# SECDONGL_001.net
KiCad netlist of a schematic drawn in EAGLE
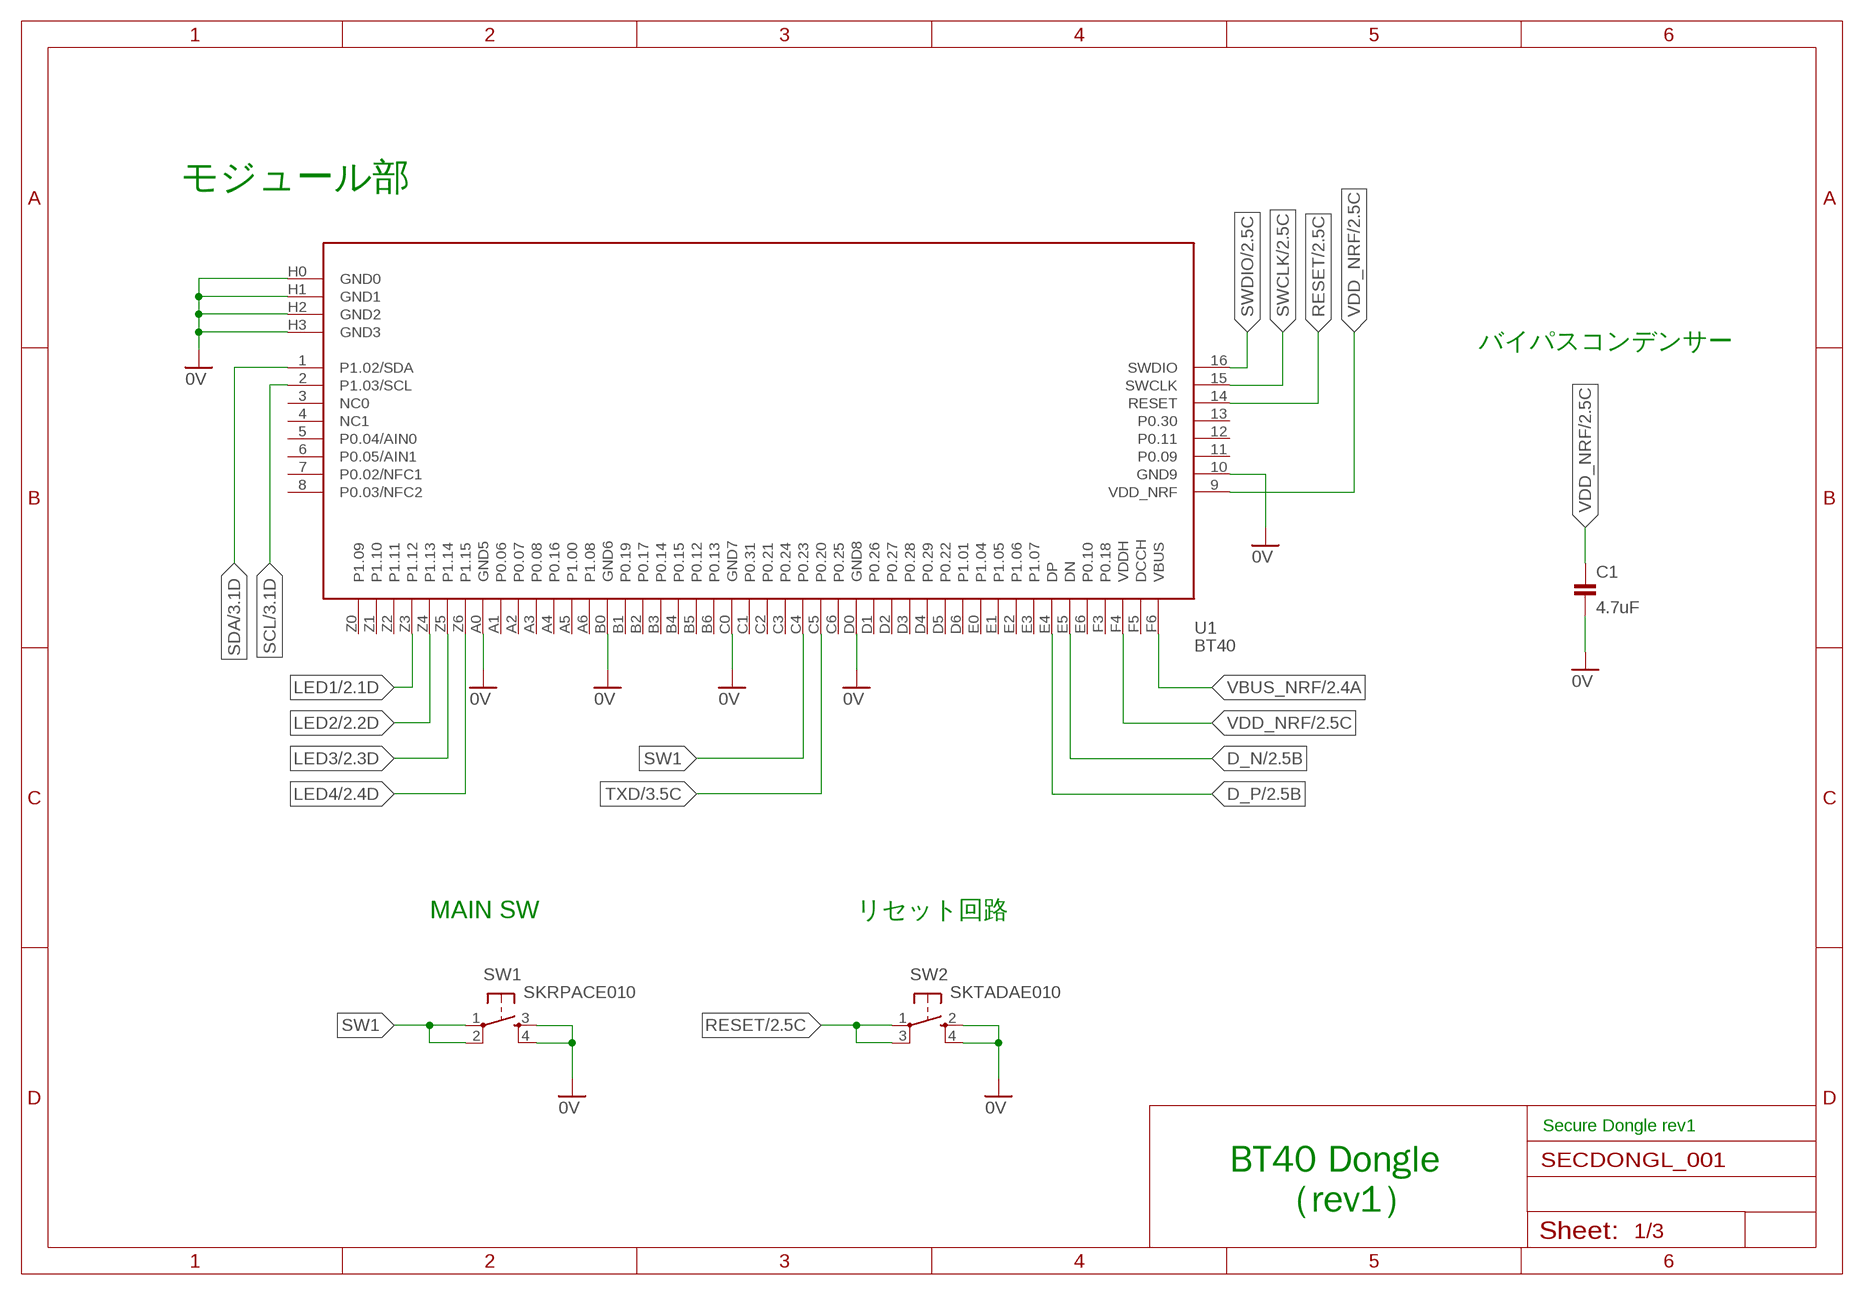
[diagram p0: schematic, sheet 1]
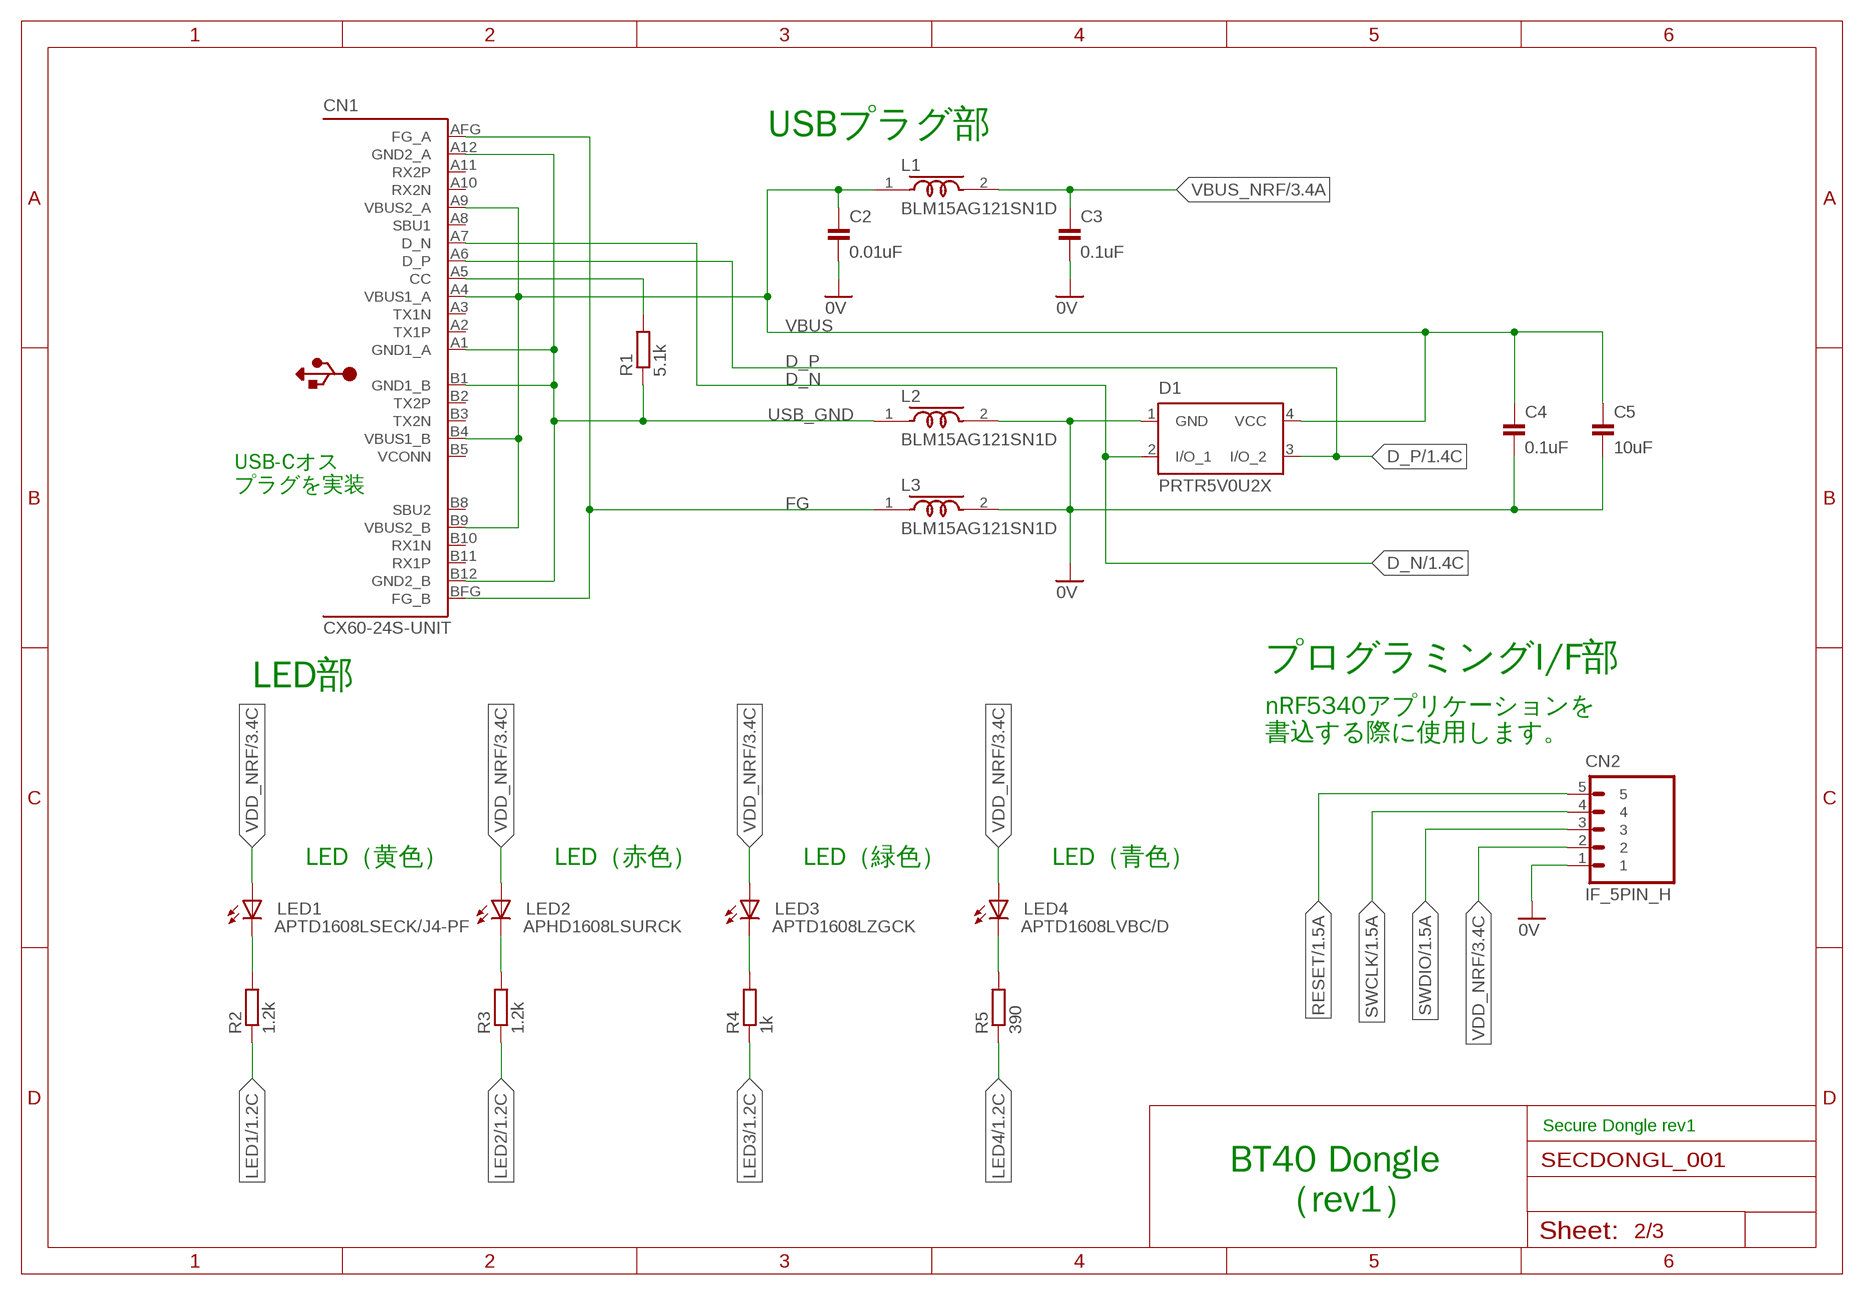
[diagram p1: schematic, sheet 2]
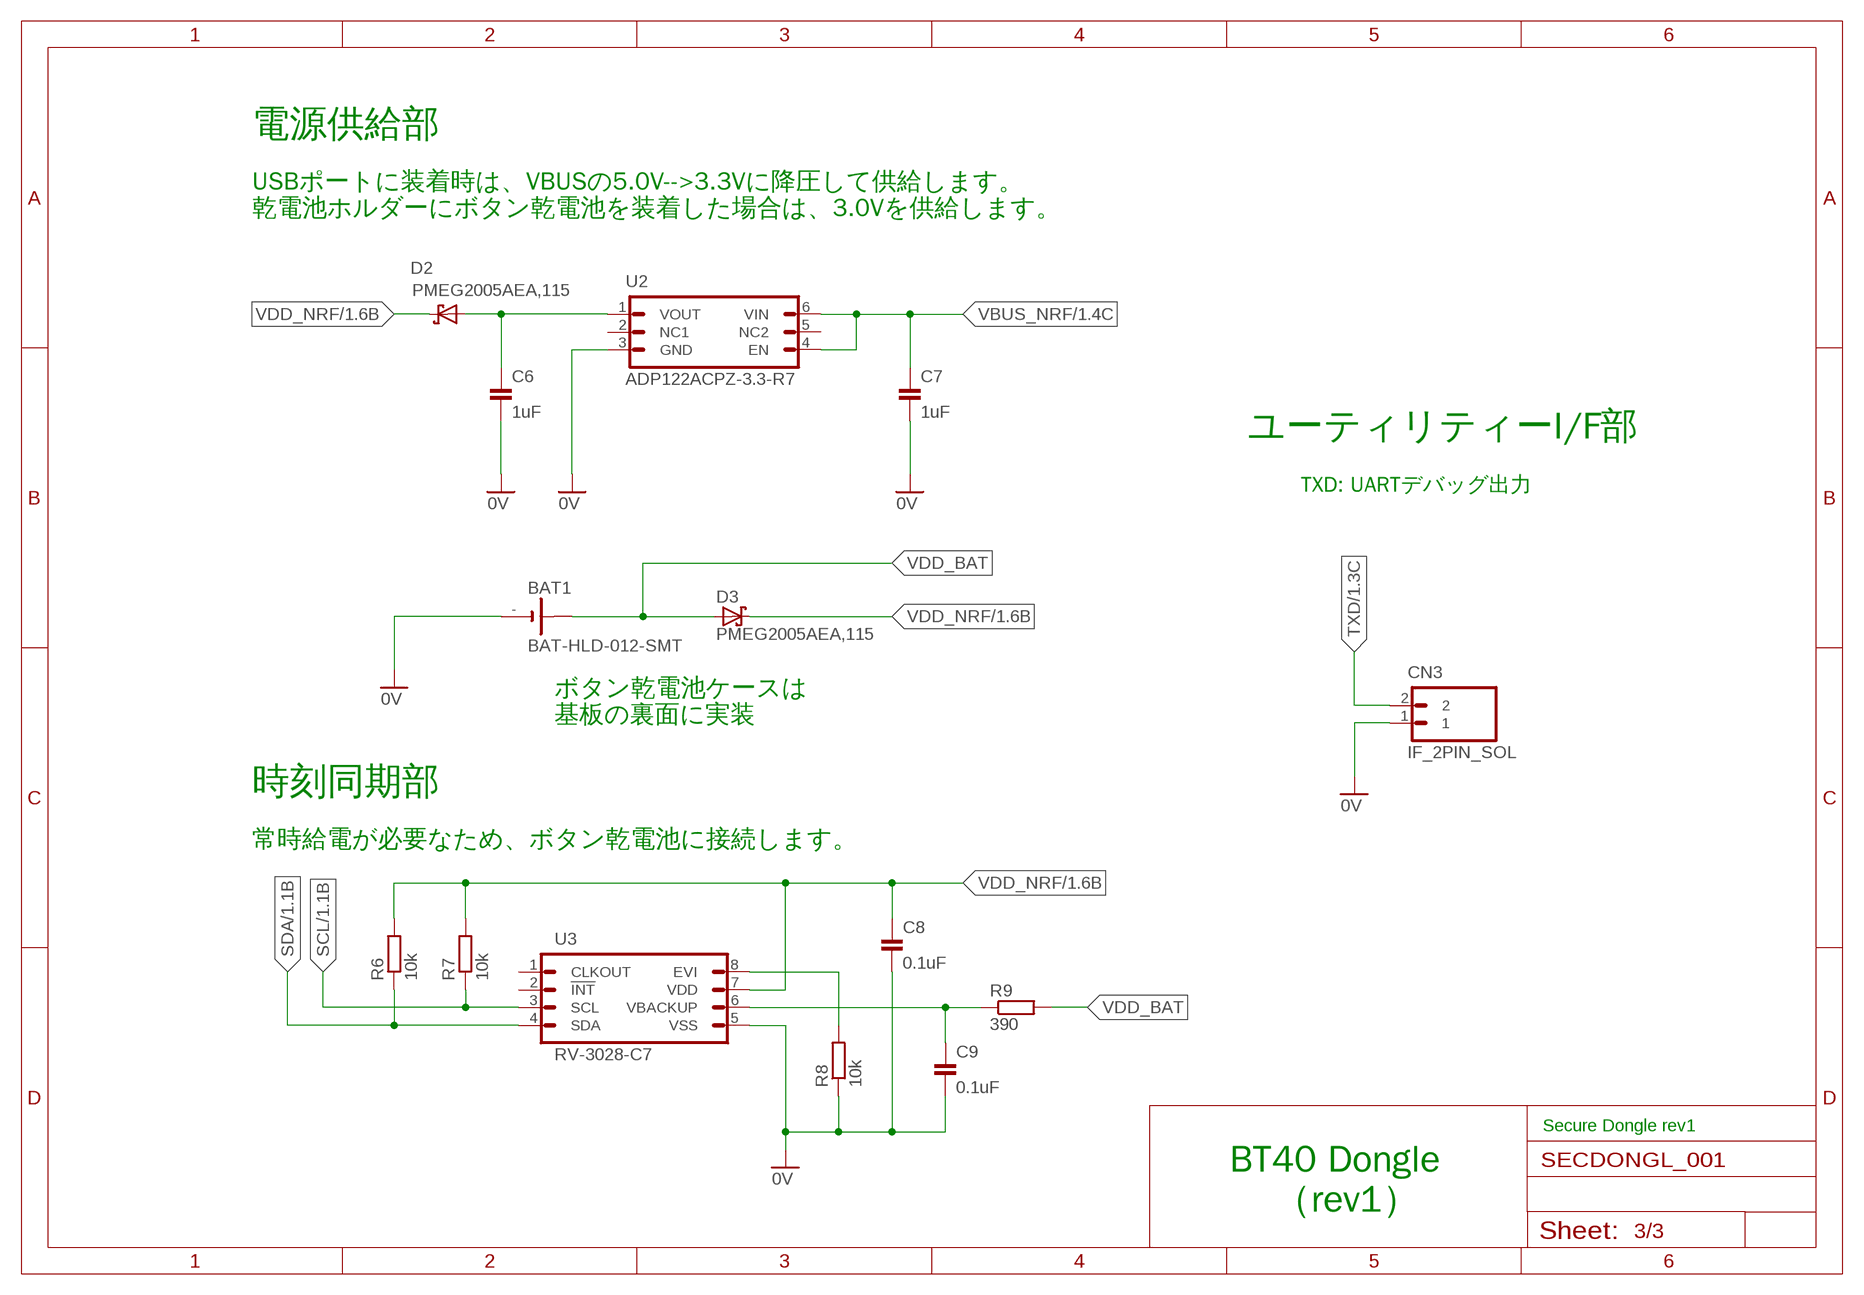
[diagram p2: schematic, sheet 3]

(export (version "E")
  (design (tool "Eeschema 10.0.6"))
  (components
    (comp (ref "BAT1")
      (value "BAT-HLD-012-SMT")
      (footprint "eagle-import:BAT-HLD-012-SMT")
      (libsource (lib "eagle-import") (part "BAT-HLD-012-SMT"))
    )
    (comp (ref "C6")
      (value "1uF")
      (footprint "eagle-import:C0603K")
      (libsource (lib "eagle-import") (part "CAP_0603"))
    )
    (comp (ref "C7")
      (value "1uF")
      (footprint "eagle-import:C0603K")
      (libsource (lib "eagle-import") (part "CAP_0603"))
    )
    (comp (ref "C8")
      (value "0.1uF")
      (footprint "eagle-import:C0402K")
      (libsource (lib "eagle-import") (part "CAP_0402K"))
    )
    (comp (ref "C9")
      (value "0.1uF")
      (footprint "eagle-import:C0402K")
      (libsource (lib "eagle-import") (part "CAP_0402K"))
    )
    (comp (ref "CN3")
      (value "IF_2PIN_SOL")
      (footprint "eagle-import:SOLPAD_2PIN")
      (libsource (lib "eagle-import") (part "IF_2PIN_SOL"))
    )
    (comp (ref "D2")
      (value "PMEG2005AEA,115")
      (footprint "eagle-import:SOD323-W")
      (libsource (lib "eagle-import") (part "PMEG2005AEA,115"))
    )
    (comp (ref "D3")
      (value "PMEG2005AEA,115")
      (footprint "eagle-import:SOD323-W")
      (libsource (lib "eagle-import") (part "PMEG2005AEA,115"))
    )
    (comp (ref "R6")
      (value "10k")
      (footprint "eagle-import:R0402")
      (libsource (lib "eagle-import") (part "RESISTOR_0402"))
    )
    (comp (ref "R7")
      (value "10k")
      (footprint "eagle-import:R0402")
      (libsource (lib "eagle-import") (part "RESISTOR_0402"))
    )
    (comp (ref "R8")
      (value "10k")
      (footprint "eagle-import:R0402")
      (libsource (lib "eagle-import") (part "RESISTOR_0402"))
    )
    (comp (ref "R9")
      (value "390")
      (footprint "eagle-import:R0402")
      (libsource (lib "eagle-import") (part "RESISTOR_0402"))
    )
    (comp (ref "U2")
      (value "ADP122ACPZ-3.3-R7")
      (footprint "eagle-import:6-LFCSP_UD")
      (libsource (lib "eagle-import") (part "ADP122ACPZ-3.3-R7"))
    )
    (comp (ref "U3")
      (value "RV-3028-C7")
      (footprint "eagle-import:SON-8")
      (libsource (lib "eagle-import") (part "RV-3028-C7"))
    )
    (comp (ref "C1")
      (value "4.7uF")
      (footprint "eagle-import:C0603K")
      (libsource (lib "eagle-import") (part "CAP_0603"))
    )
    (comp (ref "SW1")
      (value "SKRPACE010")
      (footprint "eagle-import:SKRPACE010")
      (libsource (lib "eagle-import") (part "SKRPACE010"))
    )
    (comp (ref "SW2")
      (value "SKTADAE010")
      (footprint "eagle-import:SKTADAE010")
      (libsource (lib "eagle-import") (part "SKTADAE010"))
    )
    (comp (ref "U1")
      (value "BT40")
      (footprint "eagle-import:BM40-B_1PRIMARY")
      (libsource (lib "eagle-import") (part "BT40"))
    )
    (comp (ref "C2")
      (value "0.01uF")
      (footprint "eagle-import:C0402K")
      (libsource (lib "eagle-import") (part "CAP_0402K"))
    )
    (comp (ref "C3")
      (value "0.1uF")
      (footprint "eagle-import:C0402K")
      (libsource (lib "eagle-import") (part "CAP_0402K"))
    )
    (comp (ref "C4")
      (value "0.1uF")
      (footprint "eagle-import:C0402K")
      (libsource (lib "eagle-import") (part "CAP_0402K"))
    )
    (comp (ref "C5")
      (value "10uF")
      (footprint "eagle-import:C0603K")
      (libsource (lib "eagle-import") (part "CAP_0603"))
    )
    (comp (ref "CN1")
      (value "CX60-24S-UNIT")
      (footprint "eagle-import:CX60-24S-UNIT")
      (libsource (lib "eagle-import") (part "CX60-24S-UNIT"))
    )
    (comp (ref "CN2")
      (value "IF_5PIN_H")
      (footprint "eagle-import:HEADER_5PIN")
      (libsource (lib "eagle-import") (part "IF_5PIN_H"))
    )
    (comp (ref "D1")
      (value "PRTR5V0U2X")
      (footprint "eagle-import:SOT143B")
      (libsource (lib "eagle-import") (part "PRTR5V0U2X"))
    )
    (comp (ref "L1")
      (value "BLM15AG121SN1D")
      (footprint "eagle-import:C0402K")
      (libsource (lib "eagle-import") (part "BLM15AG121SN1D"))
    )
    (comp (ref "L2")
      (value "BLM15AG121SN1D")
      (footprint "eagle-import:C0402K")
      (libsource (lib "eagle-import") (part "BLM15AG121SN1D"))
    )
    (comp (ref "L3")
      (value "BLM15AG121SN1D")
      (footprint "eagle-import:C0402K")
      (libsource (lib "eagle-import") (part "BLM15AG121SN1D"))
    )
    (comp (ref "LED1")
      (value "APTD1608LSECK/J4-PF")
      (footprint "eagle-import:APTD1608")
      (libsource (lib "eagle-import") (part "APTD1608LSECK/J4-PF"))
    )
    (comp (ref "LED2")
      (value "APHD1608LSURCK")
      (footprint "eagle-import:APTD1608")
      (libsource (lib "eagle-import") (part "APHD1608LSURCK"))
    )
    (comp (ref "LED3")
      (value "APTD1608LZGCK")
      (footprint "eagle-import:APTD1608")
      (libsource (lib "eagle-import") (part "APTD1608LZGCK"))
    )
    (comp (ref "LED4")
      (value "APTD1608LVBC/D")
      (footprint "eagle-import:APTD1608")
      (libsource (lib "eagle-import") (part "APTD1608LVBC/D"))
    )
    (comp (ref "R1")
      (value "5.1k")
      (footprint "eagle-import:R0402")
      (libsource (lib "eagle-import") (part "RESISTOR_0402"))
    )
    (comp (ref "R2")
      (value "1.2k")
      (footprint "eagle-import:R0402")
      (libsource (lib "eagle-import") (part "RESISTOR_0402"))
    )
    (comp (ref "R3")
      (value "1.2k")
      (footprint "eagle-import:R0402")
      (libsource (lib "eagle-import") (part "RESISTOR_0402"))
    )
    (comp (ref "R4")
      (value "1k")
      (footprint "eagle-import:R0402")
      (libsource (lib "eagle-import") (part "RESISTOR_0402"))
    )
    (comp (ref "R5")
      (value "390")
      (footprint "eagle-import:R0402")
      (libsource (lib "eagle-import") (part "RESISTOR_0402"))
    )
  )
  (nets
    (net (code "1") (name "0V") (class "Default")
      (node (ref "BAT1") (pin "-") (pinfunction "-_-") (pintype "passive"))
      (node (ref "C1") (pin "2") (pinfunction "2_2") (pintype "passive"))
      (node (ref "C2") (pin "2") (pinfunction "2_2") (pintype "passive"))
      (node (ref "C3") (pin "2") (pinfunction "2_2") (pintype "passive"))
      (node (ref "C4") (pin "2") (pinfunction "2_2") (pintype "passive"))
      (node (ref "C5") (pin "2") (pinfunction "2_2") (pintype "passive"))
      (node (ref "C6") (pin "2") (pinfunction "2_2") (pintype "passive"))
      (node (ref "C7") (pin "2") (pinfunction "2_2") (pintype "passive"))
      (node (ref "C8") (pin "2") (pinfunction "2_2") (pintype "passive"))
      (node (ref "C9") (pin "2") (pinfunction "2_2") (pintype "passive"))
      (node (ref "CN2") (pin "1") (pinfunction "1_1") (pintype "passive"))
      (node (ref "CN3") (pin "1") (pinfunction "1_1") (pintype "passive"))
      (node (ref "D1") (pin "1") (pinfunction "GND_1") (pintype "passive"))
      (node (ref "L2") (pin "2") (pinfunction "2_2") (pintype "passive"))
      (node (ref "L3") (pin "2") (pinfunction "2_2") (pintype "passive"))
      (node (ref "R8") (pin "1") (pinfunction "1_1") (pintype "passive"))
      (node (ref "SW1") (pin "3") (pinfunction "S_3") (pintype "passive"))
      (node (ref "SW1") (pin "4") (pinfunction "S1_4") (pintype "passive"))
      (node (ref "SW2") (pin "2") (pinfunction "S_2") (pintype "passive"))
      (node (ref "SW2") (pin "4") (pinfunction "S1_4") (pintype "passive"))
      (node (ref "U1") (pin "10") (pinfunction "GND9_10") (pintype "passive"))
      (node (ref "U1") (pin "A0") (pinfunction "GND5_A0") (pintype "passive"))
      (node (ref "U1") (pin "B0") (pinfunction "GND6_B0") (pintype "passive"))
      (node (ref "U1") (pin "C0") (pinfunction "GND7_C0") (pintype "passive"))
      (node (ref "U1") (pin "D0") (pinfunction "GND8_D0") (pintype "passive"))
      (node (ref "U1") (pin "H0") (pinfunction "GND0_H0") (pintype "passive"))
      (node (ref "U1") (pin "H1") (pinfunction "GND1_H1") (pintype "passive"))
      (node (ref "U1") (pin "H2") (pinfunction "GND2_H2") (pintype "passive"))
      (node (ref "U1") (pin "H3") (pinfunction "GND3_H3") (pintype "passive"))
      (node (ref "U2") (pin "3") (pinfunction "GND_3") (pintype "passive"))
      (node (ref "U3") (pin "5") (pinfunction "VSS_5") (pintype "passive"))
    )
    (net (code "2") (name "D_N") (class "Default")
      (node (ref "CN1") (pin "A7") (pinfunction "D_N_A7") (pintype "bidirectional"))
      (node (ref "D1") (pin "2") (pinfunction "I/O_1_2") (pintype "bidirectional"))
      (node (ref "U1") (pin "E5") (pinfunction "DN_E5") (pintype "bidirectional"))
    )
    (net (code "3") (name "D_P") (class "Default")
      (node (ref "CN1") (pin "A6") (pinfunction "D_P_A6") (pintype "bidirectional"))
      (node (ref "D1") (pin "3") (pinfunction "I/O_2_3") (pintype "bidirectional"))
      (node (ref "U1") (pin "E4") (pinfunction "DP_E4") (pintype "bidirectional"))
    )
    (net (code "4") (name "FG") (class "Default")
      (node (ref "CN1") (pin "AFG") (pinfunction "FG_A_AFG") (pintype "passive"))
      (node (ref "CN1") (pin "BFG") (pinfunction "FG_B_BFG") (pintype "passive"))
      (node (ref "L3") (pin "1") (pinfunction "1_1") (pintype "passive"))
    )
    (net (code "5") (name "LED1") (class "Default")
      (node (ref "R2") (pin "1") (pinfunction "1_1") (pintype "passive"))
      (node (ref "U1") (pin "Z3") (pinfunction "P1.12_Z3") (pintype "bidirectional"))
    )
    (net (code "6") (name "LED2") (class "Default")
      (node (ref "R3") (pin "1") (pinfunction "1_1") (pintype "passive"))
      (node (ref "U1") (pin "Z4") (pinfunction "P1.13_Z4") (pintype "bidirectional"))
    )
    (net (code "7") (name "LED3") (class "Default")
      (node (ref "R4") (pin "1") (pinfunction "1_1") (pintype "passive"))
      (node (ref "U1") (pin "Z5") (pinfunction "P1.14_Z5") (pintype "bidirectional"))
    )
    (net (code "8") (name "LED4") (class "Default")
      (node (ref "R5") (pin "1") (pinfunction "1_1") (pintype "passive"))
      (node (ref "U1") (pin "Z6") (pinfunction "P1.15_Z6") (pintype "bidirectional"))
    )
    (net (code "9") (name "Net-(CN1-CC)") (class "Default")
      (node (ref "CN1") (pin "A5") (pinfunction "CC_A5") (pintype "passive"))
      (node (ref "R1") (pin "2") (pinfunction "2_2") (pintype "passive"))
    )
    (net (code "10") (name "Net-(LED1-PadC)") (class "Default")
      (node (ref "LED1") (pin "C") (pinfunction "C_C") (pintype "passive"))
      (node (ref "R2") (pin "2") (pinfunction "2_2") (pintype "passive"))
    )
    (net (code "11") (name "Net-(LED2-PadC)") (class "Default")
      (node (ref "LED2") (pin "C") (pinfunction "C_C") (pintype "passive"))
      (node (ref "R3") (pin "2") (pinfunction "2_2") (pintype "passive"))
    )
    (net (code "12") (name "Net-(LED3-PadC)") (class "Default")
      (node (ref "LED3") (pin "C") (pinfunction "C_C") (pintype "passive"))
      (node (ref "R4") (pin "2") (pinfunction "2_2") (pintype "passive"))
    )
    (net (code "13") (name "Net-(LED4-PadC)") (class "Default")
      (node (ref "LED4") (pin "C") (pinfunction "C_C") (pintype "passive"))
      (node (ref "R5") (pin "2") (pinfunction "2_2") (pintype "passive"))
    )
    (net (code "14") (name "Net-(U2-VOUT)") (class "Default")
      (node (ref "C6") (pin "1") (pinfunction "1_1") (pintype "passive"))
      (node (ref "D2") (pin "A") (pinfunction "A_A") (pintype "passive"))
      (node (ref "U2") (pin "1") (pinfunction "VOUT_1") (pintype "passive"))
    )
    (net (code "15") (name "Net-(U3-EVI)") (class "Default")
      (node (ref "R8") (pin "2") (pinfunction "2_2") (pintype "passive"))
      (node (ref "U3") (pin "8") (pinfunction "EVI_8") (pintype "bidirectional"))
    )
    (net (code "16") (name "Net-(U3-VBACKUP)") (class "Default")
      (node (ref "C9") (pin "1") (pinfunction "1_1") (pintype "passive"))
      (node (ref "R9") (pin "1") (pinfunction "1_1") (pintype "passive"))
      (node (ref "U3") (pin "6") (pinfunction "VBACKUP_6") (pintype "passive"))
    )
    (net (code "17") (name "RESET") (class "Default")
      (node (ref "CN2") (pin "5") (pinfunction "5_5") (pintype "passive"))
      (node (ref "SW2") (pin "1") (pinfunction "P_1") (pintype "passive"))
      (node (ref "SW2") (pin "3") (pinfunction "P1_3") (pintype "passive"))
      (node (ref "U1") (pin "14") (pinfunction "RESET_14") (pintype "bidirectional"))
    )
    (net (code "18") (name "SCL") (class "Default")
      (node (ref "R7") (pin "1") (pinfunction "1_1") (pintype "passive"))
      (node (ref "U1") (pin "2") (pinfunction "P1.03/SCL_2") (pintype "bidirectional"))
      (node (ref "U3") (pin "3") (pinfunction "SCL_3") (pintype "bidirectional"))
    )
    (net (code "19") (name "SDA") (class "Default")
      (node (ref "R6") (pin "1") (pinfunction "1_1") (pintype "passive"))
      (node (ref "U1") (pin "1") (pinfunction "P1.02/SDA_1") (pintype "bidirectional"))
      (node (ref "U3") (pin "4") (pinfunction "SDA_4") (pintype "bidirectional"))
    )
    (net (code "20") (name "SW1") (class "Default")
      (node (ref "SW1") (pin "1") (pinfunction "P_1") (pintype "passive"))
      (node (ref "SW1") (pin "2") (pinfunction "P1_2") (pintype "passive"))
      (node (ref "U1") (pin "C4") (pinfunction "P0.23_C4") (pintype "bidirectional"))
    )
    (net (code "21") (name "SWCLK") (class "Default")
      (node (ref "CN2") (pin "4") (pinfunction "4_4") (pintype "passive"))
      (node (ref "U1") (pin "15") (pinfunction "SWCLK_15") (pintype "bidirectional"))
    )
    (net (code "22") (name "SWDIO") (class "Default")
      (node (ref "CN2") (pin "3") (pinfunction "3_3") (pintype "passive"))
      (node (ref "U1") (pin "16") (pinfunction "SWDIO_16") (pintype "bidirectional"))
    )
    (net (code "23") (name "TXD") (class "Default")
      (node (ref "CN3") (pin "2") (pinfunction "2_2") (pintype "passive"))
      (node (ref "U1") (pin "C5") (pinfunction "P0.20_C5") (pintype "bidirectional"))
    )
    (net (code "24") (name "USB_GND") (class "Default")
      (node (ref "CN1") (pin "A1") (pinfunction "GND1_A_A1") (pintype "passive"))
      (node (ref "CN1") (pin "A12") (pinfunction "GND2_A_A12") (pintype "bidirectional"))
      (node (ref "CN1") (pin "B1") (pinfunction "GND1_B_B1") (pintype "passive"))
      (node (ref "CN1") (pin "B12") (pinfunction "GND2_B_B12") (pintype "passive"))
      (node (ref "L2") (pin "1") (pinfunction "1_1") (pintype "passive"))
      (node (ref "R1") (pin "1") (pinfunction "1_1") (pintype "passive"))
    )
    (net (code "25") (name "VBUS") (class "Default")
      (node (ref "C2") (pin "1") (pinfunction "1_1") (pintype "passive"))
      (node (ref "C4") (pin "1") (pinfunction "1_1") (pintype "passive"))
      (node (ref "C5") (pin "1") (pinfunction "1_1") (pintype "passive"))
      (node (ref "CN1") (pin "A4") (pinfunction "VBUS1_A_A4") (pintype "passive"))
      (node (ref "CN1") (pin "A9") (pinfunction "VBUS2_A_A9") (pintype "passive"))
      (node (ref "CN1") (pin "B4") (pinfunction "VBUS1_B_B4") (pintype "passive"))
      (node (ref "CN1") (pin "B9") (pinfunction "VBUS2_B_B9") (pintype "passive"))
      (node (ref "D1") (pin "4") (pinfunction "VCC_4") (pintype "passive"))
      (node (ref "L1") (pin "1") (pinfunction "1_1") (pintype "passive"))
    )
    (net (code "26") (name "VBUS_NRF") (class "Default")
      (node (ref "C3") (pin "1") (pinfunction "1_1") (pintype "passive"))
      (node (ref "C7") (pin "1") (pinfunction "1_1") (pintype "passive"))
      (node (ref "L1") (pin "2") (pinfunction "2_2") (pintype "passive"))
      (node (ref "U1") (pin "F6") (pinfunction "VBUS_F6") (pintype "passive"))
      (node (ref "U2") (pin "4") (pinfunction "EN_4") (pintype "bidirectional"))
      (node (ref "U2") (pin "6") (pinfunction "VIN_6") (pintype "passive"))
    )
    (net (code "27") (name "VDD_BAT") (class "Default")
      (node (ref "BAT1") (pin "+@2") (pinfunction "+_+@2") (pintype "passive"))
      (node (ref "D3") (pin "A") (pinfunction "A_A") (pintype "passive"))
      (node (ref "R9") (pin "2") (pinfunction "2_2") (pintype "passive"))
    )
    (net (code "28") (name "VDD_NRF") (class "Default")
      (node (ref "C1") (pin "1") (pinfunction "1_1") (pintype "passive"))
      (node (ref "C8") (pin "1") (pinfunction "1_1") (pintype "passive"))
      (node (ref "CN2") (pin "2") (pinfunction "2_2") (pintype "passive"))
      (node (ref "D2") (pin "C") (pinfunction "C_C") (pintype "passive"))
      (node (ref "D3") (pin "C") (pinfunction "C_C") (pintype "passive"))
      (node (ref "LED1") (pin "A") (pinfunction "A_A") (pintype "passive"))
      (node (ref "LED2") (pin "A") (pinfunction "A_A") (pintype "passive"))
      (node (ref "LED3") (pin "A") (pinfunction "A_A") (pintype "passive"))
      (node (ref "LED4") (pin "A") (pinfunction "A_A") (pintype "passive"))
      (node (ref "R6") (pin "2") (pinfunction "2_2") (pintype "passive"))
      (node (ref "R7") (pin "2") (pinfunction "2_2") (pintype "passive"))
      (node (ref "U1") (pin "9") (pinfunction "VDD_NRF_9") (pintype "passive"))
      (node (ref "U1") (pin "F4") (pinfunction "VDDH_F4") (pintype "passive"))
      (node (ref "U3") (pin "7") (pinfunction "VDD_7") (pintype "passive"))
    )
    (net (code "29") (name "unconnected-(CN1-RX1N-PadB10)") (class "Default")
      (node (ref "CN1") (pin "B10") (pinfunction "RX1N_B10") (pintype "bidirectional"))
    )
    (net (code "30") (name "unconnected-(CN1-RX1P-PadB11)") (class "Default")
      (node (ref "CN1") (pin "B11") (pinfunction "RX1P_B11") (pintype "bidirectional"))
    )
    (net (code "31") (name "unconnected-(CN1-RX2N-PadA10)") (class "Default")
      (node (ref "CN1") (pin "A10") (pinfunction "RX2N_A10") (pintype "passive"))
    )
    (net (code "32") (name "unconnected-(CN1-RX2P-PadA11)") (class "Default")
      (node (ref "CN1") (pin "A11") (pinfunction "RX2P_A11") (pintype "bidirectional"))
    )
    (net (code "33") (name "unconnected-(CN1-SBU1-PadA8)") (class "Default")
      (node (ref "CN1") (pin "A8") (pinfunction "SBU1_A8") (pintype "passive"))
    )
    (net (code "34") (name "unconnected-(CN1-SBU2-PadB8)") (class "Default")
      (node (ref "CN1") (pin "B8") (pinfunction "SBU2_B8") (pintype "passive"))
    )
    (net (code "35") (name "unconnected-(CN1-TX1N-PadA3)") (class "Default")
      (node (ref "CN1") (pin "A3") (pinfunction "TX1N_A3") (pintype "bidirectional"))
    )
    (net (code "36") (name "unconnected-(CN1-TX1P-PadA2)") (class "Default")
      (node (ref "CN1") (pin "A2") (pinfunction "TX1P_A2") (pintype "bidirectional"))
    )
    (net (code "37") (name "unconnected-(CN1-TX2N-PadB3)") (class "Default")
      (node (ref "CN1") (pin "B3") (pinfunction "TX2N_B3") (pintype "bidirectional"))
    )
    (net (code "38") (name "unconnected-(CN1-TX2P-PadB2)") (class "Default")
      (node (ref "CN1") (pin "B2") (pinfunction "TX2P_B2") (pintype "bidirectional"))
    )
    (net (code "39") (name "unconnected-(CN1-VCONN-PadB5)") (class "Default")
      (node (ref "CN1") (pin "B5") (pinfunction "VCONN_B5") (pintype "passive"))
    )
    (net (code "40") (name "unconnected-(U1-DCCH-PadF5)") (class "Default")
      (node (ref "U1") (pin "F5") (pinfunction "DCCH_F5") (pintype "passive"))
    )
    (net (code "41") (name "unconnected-(U1-NC0-Pad3)") (class "Default")
      (node (ref "U1") (pin "3") (pinfunction "NC0_3") (pintype "no_connect"))
    )
    (net (code "42") (name "unconnected-(U1-NC1-Pad4)") (class "Default")
      (node (ref "U1") (pin "4") (pinfunction "NC1_4") (pintype "no_connect"))
    )
    (net (code "43") (name "unconnected-(U1-P0.02{slash}NFC1-Pad7)") (class "Default")
      (node (ref "U1") (pin "7") (pinfunction "P0.02/NFC1_7") (pintype "bidirectional"))
    )
    (net (code "44") (name "unconnected-(U1-P0.03{slash}NFC2-Pad8)") (class "Default")
      (node (ref "U1") (pin "8") (pinfunction "P0.03/NFC2_8") (pintype "bidirectional"))
    )
    (net (code "45") (name "unconnected-(U1-P0.04{slash}AIN0-Pad5)") (class "Default")
      (node (ref "U1") (pin "5") (pinfunction "P0.04/AIN0_5") (pintype "bidirectional"))
    )
    (net (code "46") (name "unconnected-(U1-P0.05{slash}AIN1-Pad6)") (class "Default")
      (node (ref "U1") (pin "6") (pinfunction "P0.05/AIN1_6") (pintype "bidirectional"))
    )
    (net (code "47") (name "unconnected-(U1-P0.06-PadA1)") (class "Default")
      (node (ref "U1") (pin "A1") (pinfunction "P0.06_A1") (pintype "bidirectional"))
    )
    (net (code "48") (name "unconnected-(U1-P0.07-PadA2)") (class "Default")
      (node (ref "U1") (pin "A2") (pinfunction "P0.07_A2") (pintype "bidirectional"))
    )
    (net (code "49") (name "unconnected-(U1-P0.08-PadA3)") (class "Default")
      (node (ref "U1") (pin "A3") (pinfunction "P0.08_A3") (pintype "bidirectional"))
    )
    (net (code "50") (name "unconnected-(U1-P0.09-Pad11)") (class "Default")
      (node (ref "U1") (pin "11") (pinfunction "P0.09_11") (pintype "bidirectional"))
    )
    (net (code "51") (name "unconnected-(U1-P0.10-PadE6)") (class "Default")
      (node (ref "U1") (pin "E6") (pinfunction "P0.10_E6") (pintype "bidirectional"))
    )
    (net (code "52") (name "unconnected-(U1-P0.11-Pad12)") (class "Default")
      (node (ref "U1") (pin "12") (pinfunction "P0.11_12") (pintype "bidirectional"))
    )
    (net (code "53") (name "unconnected-(U1-P0.12-PadB5)") (class "Default")
      (node (ref "U1") (pin "B5") (pinfunction "P0.12_B5") (pintype "bidirectional"))
    )
    (net (code "54") (name "unconnected-(U1-P0.13-PadB6)") (class "Default")
      (node (ref "U1") (pin "B6") (pinfunction "P0.13_B6") (pintype "bidirectional"))
    )
    (net (code "55") (name "unconnected-(U1-P0.14-PadB3)") (class "Default")
      (node (ref "U1") (pin "B3") (pinfunction "P0.14_B3") (pintype "bidirectional"))
    )
    (net (code "56") (name "unconnected-(U1-P0.15-PadB4)") (class "Default")
      (node (ref "U1") (pin "B4") (pinfunction "P0.15_B4") (pintype "bidirectional"))
    )
    (net (code "57") (name "unconnected-(U1-P0.16-PadA4)") (class "Default")
      (node (ref "U1") (pin "A4") (pinfunction "P0.16_A4") (pintype "bidirectional"))
    )
    (net (code "58") (name "unconnected-(U1-P0.17-PadB2)") (class "Default")
      (node (ref "U1") (pin "B2") (pinfunction "P0.17_B2") (pintype "bidirectional"))
    )
    (net (code "59") (name "unconnected-(U1-P0.18-PadF3)") (class "Default")
      (node (ref "U1") (pin "F3") (pinfunction "P0.18_F3") (pintype "bidirectional"))
    )
    (net (code "60") (name "unconnected-(U1-P0.19-PadB1)") (class "Default")
      (node (ref "U1") (pin "B1") (pinfunction "P0.19_B1") (pintype "bidirectional"))
    )
    (net (code "61") (name "unconnected-(U1-P0.21-PadC2)") (class "Default")
      (node (ref "U1") (pin "C2") (pinfunction "P0.21_C2") (pintype "bidirectional"))
    )
    (net (code "62") (name "unconnected-(U1-P0.22-PadD5)") (class "Default")
      (node (ref "U1") (pin "D5") (pinfunction "P0.22_D5") (pintype "bidirectional"))
    )
    (net (code "63") (name "unconnected-(U1-P0.24-PadC3)") (class "Default")
      (node (ref "U1") (pin "C3") (pinfunction "P0.24_C3") (pintype "bidirectional"))
    )
    (net (code "64") (name "unconnected-(U1-P0.25-PadC6)") (class "Default")
      (node (ref "U1") (pin "C6") (pinfunction "P0.25_C6") (pintype "bidirectional"))
    )
    (net (code "65") (name "unconnected-(U1-P0.26-PadD1)") (class "Default")
      (node (ref "U1") (pin "D1") (pinfunction "P0.26_D1") (pintype "bidirectional"))
    )
    (net (code "66") (name "unconnected-(U1-P0.27-PadD2)") (class "Default")
      (node (ref "U1") (pin "D2") (pinfunction "P0.27_D2") (pintype "bidirectional"))
    )
    (net (code "67") (name "unconnected-(U1-P0.28-PadD3)") (class "Default")
      (node (ref "U1") (pin "D3") (pinfunction "P0.28_D3") (pintype "bidirectional"))
    )
    (net (code "68") (name "unconnected-(U1-P0.29-PadD4)") (class "Default")
      (node (ref "U1") (pin "D4") (pinfunction "P0.29_D4") (pintype "bidirectional"))
    )
    (net (code "69") (name "unconnected-(U1-P0.30-Pad13)") (class "Default")
      (node (ref "U1") (pin "13") (pinfunction "P0.30_13") (pintype "bidirectional"))
    )
    (net (code "70") (name "unconnected-(U1-P0.31-PadC1)") (class "Default")
      (node (ref "U1") (pin "C1") (pinfunction "P0.31_C1") (pintype "bidirectional"))
    )
    (net (code "71") (name "unconnected-(U1-P1.00-PadA5)") (class "Default")
      (node (ref "U1") (pin "A5") (pinfunction "P1.00_A5") (pintype "bidirectional"))
    )
    (net (code "72") (name "unconnected-(U1-P1.01-PadD6)") (class "Default")
      (node (ref "U1") (pin "D6") (pinfunction "P1.01_D6") (pintype "bidirectional"))
    )
    (net (code "73") (name "unconnected-(U1-P1.04-PadE0)") (class "Default")
      (node (ref "U1") (pin "E0") (pinfunction "P1.04_E0") (pintype "bidirectional"))
    )
    (net (code "74") (name "unconnected-(U1-P1.05-PadE1)") (class "Default")
      (node (ref "U1") (pin "E1") (pinfunction "P1.05_E1") (pintype "bidirectional"))
    )
    (net (code "75") (name "unconnected-(U1-P1.06-PadE2)") (class "Default")
      (node (ref "U1") (pin "E2") (pinfunction "P1.06_E2") (pintype "bidirectional"))
    )
    (net (code "76") (name "unconnected-(U1-P1.07-PadE3)") (class "Default")
      (node (ref "U1") (pin "E3") (pinfunction "P1.07_E3") (pintype "bidirectional"))
    )
    (net (code "77") (name "unconnected-(U1-P1.08-PadA6)") (class "Default")
      (node (ref "U1") (pin "A6") (pinfunction "P1.08_A6") (pintype "bidirectional"))
    )
    (net (code "78") (name "unconnected-(U1-P1.09-PadZ0)") (class "Default")
      (node (ref "U1") (pin "Z0") (pinfunction "P1.09_Z0") (pintype "bidirectional"))
    )
    (net (code "79") (name "unconnected-(U1-P1.10-PadZ1)") (class "Default")
      (node (ref "U1") (pin "Z1") (pinfunction "P1.10_Z1") (pintype "bidirectional"))
    )
    (net (code "80") (name "unconnected-(U1-P1.11-PadZ2)") (class "Default")
      (node (ref "U1") (pin "Z2") (pinfunction "P1.11_Z2") (pintype "bidirectional"))
    )
    (net (code "81") (name "unconnected-(U2-NC1-Pad2)") (class "Default")
      (node (ref "U2") (pin "2") (pinfunction "NC1_2") (pintype "passive"))
    )
    (net (code "82") (name "unconnected-(U2-NC2-Pad5)") (class "Default")
      (node (ref "U2") (pin "5") (pinfunction "NC2_5") (pintype "passive"))
    )
    (net (code "83") (name "unconnected-(U3-CLKOUT-Pad1)") (class "Default")
      (node (ref "U3") (pin "1") (pinfunction "CLKOUT_1") (pintype "bidirectional"))
    )
    (net (code "84") (name "unconnected-(U3-~{INT}-Pad2)") (class "Default")
      (node (ref "U3") (pin "2") (pinfunction "~{INT}_2") (pintype "bidirectional"))
    )
  )
)
